# square.net
KiCad netlist of a schematic drawn in EAGLE
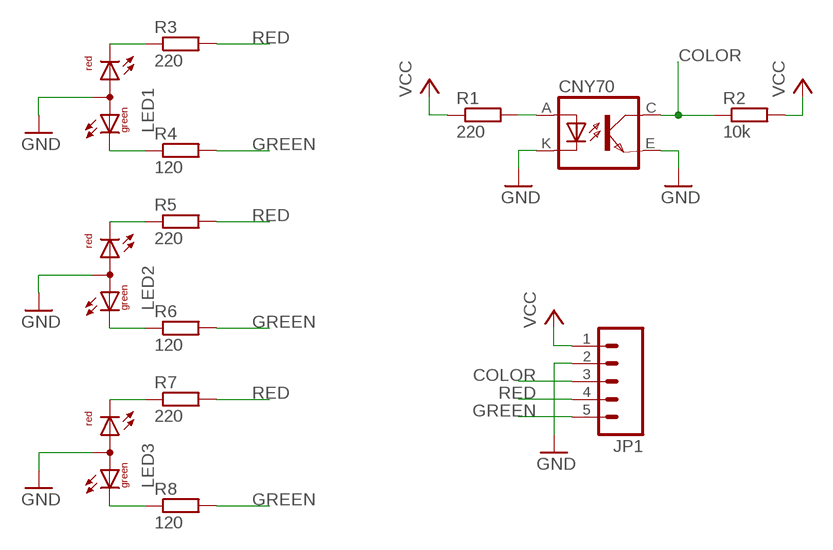
[diagram p0: schematic, sheet 1]

(export (version "E")
  (design (tool "Eeschema 10.0.6"))
  (components
    (comp (ref "CNY70")
      (value "CNY70")
      (footprint "eagle-import:4")
      (libsource (lib "eagle-import") (part "CNY70"))
    )
    (comp (ref "JP1")
      (value "M05PTH")
      (footprint "eagle-import:1X05")
      (libsource (lib "eagle-import") (part "M05PTH"))
    )
    (comp (ref "LED1")
      (value "L-115WEGW-CA")
      (footprint "eagle-import:DUOLED-A-3MM")
      (libsource (lib "eagle-import") (part "L-115WEGW-CA"))
    )
    (comp (ref "LED2")
      (value "L-115WEGW-CA")
      (footprint "eagle-import:DUOLED-A-3MM")
      (libsource (lib "eagle-import") (part "L-115WEGW-CA"))
    )
    (comp (ref "LED3")
      (value "L-115WEGW-CA")
      (footprint "eagle-import:DUOLED-A-3MM")
      (libsource (lib "eagle-import") (part "L-115WEGW-CA"))
    )
    (comp (ref "R1")
      (value "220")
      (footprint "eagle-import:0204_7")
      (libsource (lib "eagle-import") (part "R-EU_0204/7"))
    )
    (comp (ref "R2")
      (value "10k")
      (footprint "eagle-import:0204_7")
      (libsource (lib "eagle-import") (part "R-EU_0204/7"))
    )
    (comp (ref "R3")
      (value "220")
      (footprint "eagle-import:0204_7")
      (libsource (lib "eagle-import") (part "R-EU_0204/7"))
    )
    (comp (ref "R4")
      (value "120")
      (footprint "eagle-import:0204_7")
      (libsource (lib "eagle-import") (part "R-EU_0204/7"))
    )
    (comp (ref "R5")
      (value "220")
      (footprint "eagle-import:0204_7")
      (libsource (lib "eagle-import") (part "R-EU_0204/7"))
    )
    (comp (ref "R6")
      (value "120")
      (footprint "eagle-import:0204_7")
      (libsource (lib "eagle-import") (part "R-EU_0204/7"))
    )
    (comp (ref "R7")
      (value "220")
      (footprint "eagle-import:0204_7")
      (libsource (lib "eagle-import") (part "R-EU_0204/7"))
    )
    (comp (ref "R8")
      (value "120")
      (footprint "eagle-import:0204_7")
      (libsource (lib "eagle-import") (part "R-EU_0204/7"))
    )
  )
  (nets
    (net (code "1") (name "/COLOR") (class "Default")
      (node (ref "CNY70") (pin "C") (pinfunction "COL_C") (pintype "passive"))
      (node (ref "JP1") (pin "3") (pinfunction "3_3") (pintype "passive"))
      (node (ref "R2") (pin "1") (pinfunction "1_1") (pintype "passive"))
    )
    (net (code "2") (name "/GREEN") (class "Default")
      (node (ref "JP1") (pin "5") (pinfunction "5_5") (pintype "passive"))
      (node (ref "R4") (pin "2") (pinfunction "2_2") (pintype "passive"))
      (node (ref "R6") (pin "2") (pinfunction "2_2") (pintype "passive"))
      (node (ref "R8") (pin "2") (pinfunction "2_2") (pintype "passive"))
    )
    (net (code "3") (name "/RED") (class "Default")
      (node (ref "JP1") (pin "4") (pinfunction "4_4") (pintype "passive"))
      (node (ref "R3") (pin "2") (pinfunction "2_2") (pintype "passive"))
      (node (ref "R5") (pin "2") (pinfunction "2_2") (pintype "passive"))
      (node (ref "R7") (pin "2") (pinfunction "2_2") (pintype "passive"))
    )
    (net (code "4") (name "GND") (class "Default")
      (node (ref "CNY70") (pin "E") (pinfunction "EMI_E") (pintype "passive"))
      (node (ref "CNY70") (pin "K") (pinfunction "C_K") (pintype "passive"))
      (node (ref "JP1") (pin "2") (pinfunction "2_2") (pintype "passive"))
      (node (ref "LED1") (pin "2") (pinfunction "A_2") (pintype "passive"))
      (node (ref "LED2") (pin "2") (pinfunction "A_2") (pintype "passive"))
      (node (ref "LED3") (pin "2") (pinfunction "A_2") (pintype "passive"))
    )
    (net (code "5") (name "Net-(CNY70-PadA)") (class "Default")
      (node (ref "CNY70") (pin "A") (pinfunction "A_A") (pintype "passive"))
      (node (ref "R1") (pin "2") (pinfunction "2_2") (pintype "passive"))
    )
    (net (code "6") (name "Net-(LED1-CG)") (class "Default")
      (node (ref "LED1") (pin "1") (pinfunction "CG_1") (pintype "passive"))
      (node (ref "R4") (pin "1") (pinfunction "1_1") (pintype "passive"))
    )
    (net (code "7") (name "Net-(LED1-CR)") (class "Default")
      (node (ref "LED1") (pin "3") (pinfunction "CR_3") (pintype "passive"))
      (node (ref "R3") (pin "1") (pinfunction "1_1") (pintype "passive"))
    )
    (net (code "8") (name "Net-(LED2-CG)") (class "Default")
      (node (ref "LED2") (pin "1") (pinfunction "CG_1") (pintype "passive"))
      (node (ref "R6") (pin "1") (pinfunction "1_1") (pintype "passive"))
    )
    (net (code "9") (name "Net-(LED2-CR)") (class "Default")
      (node (ref "LED2") (pin "3") (pinfunction "CR_3") (pintype "passive"))
      (node (ref "R5") (pin "1") (pinfunction "1_1") (pintype "passive"))
    )
    (net (code "10") (name "Net-(LED3-CG)") (class "Default")
      (node (ref "LED3") (pin "1") (pinfunction "CG_1") (pintype "passive"))
      (node (ref "R8") (pin "1") (pinfunction "1_1") (pintype "passive"))
    )
    (net (code "11") (name "Net-(LED3-CR)") (class "Default")
      (node (ref "LED3") (pin "3") (pinfunction "CR_3") (pintype "passive"))
      (node (ref "R7") (pin "1") (pinfunction "1_1") (pintype "passive"))
    )
    (net (code "12") (name "VCC") (class "Default")
      (node (ref "JP1") (pin "1") (pinfunction "1_1") (pintype "passive"))
      (node (ref "R1") (pin "1") (pinfunction "1_1") (pintype "passive"))
      (node (ref "R2") (pin "2") (pinfunction "2_2") (pintype "passive"))
    )
  )
)
